# train-controller.net
KiCad netlist of a schematic drawn in EAGLE
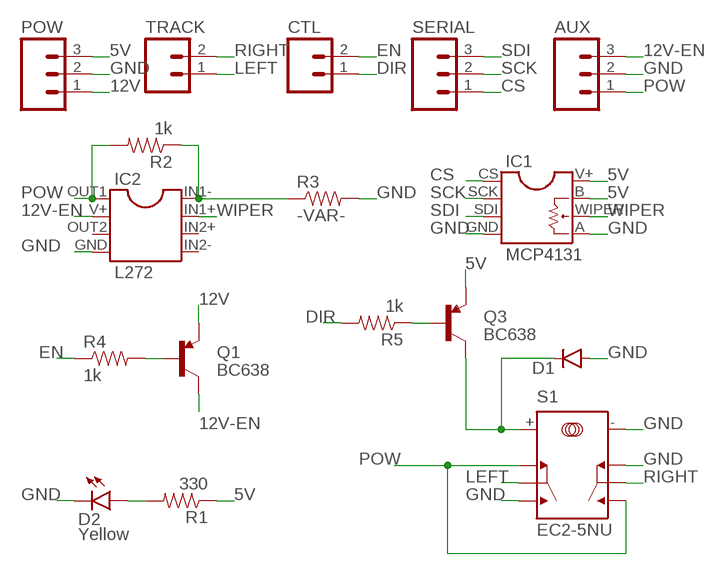
[diagram p0: schematic, sheet 1]

(export (version "E")
  (design (tool "Eeschema 10.0.6"))
  (components
    (comp (ref "AUX")
      (value "M03PTH")
      (footprint "eagle-import:1X03")
      (libsource (lib "eagle-import") (part "M03PTH"))
    )
    (comp (ref "CTL")
      (value "M02PTH")
      (footprint "eagle-import:1X02")
      (libsource (lib "eagle-import") (part "M02PTH"))
    )
    (comp (ref "D1")
      (value "DIODE1N4148")
      (footprint "eagle-import:DIODE-1N4148")
      (libsource (lib "eagle-import") (part "DIODE1N4148"))
    )
    (comp (ref "D2")
      (value "Yellow")
      (footprint "eagle-import:LED-EDGE")
      (libsource (lib "eagle-import") (part "LED-YELLOW0603"))
    )
    (comp (ref "IC1")
      (value "MCP4131")
      (footprint "eagle-import:MCP4131")
      (libsource (lib "eagle-import") (part "MCP4131"))
    )
    (comp (ref "IC2")
      (value "L272")
      (footprint "eagle-import:L272")
      (libsource (lib "eagle-import") (part "L272"))
    )
    (comp (ref "POW")
      (value "M03PTH")
      (footprint "eagle-import:1X03")
      (libsource (lib "eagle-import") (part "M03PTH"))
    )
    (comp (ref "Q1")
      (value "BC638")
      (footprint "eagle-import:TO-92")
      (libsource (lib "eagle-import") (part "TRANSISTOR_PNPTO92"))
    )
    (comp (ref "Q3")
      (value "BC638")
      (footprint "eagle-import:TO-92")
      (libsource (lib "eagle-import") (part "TRANSISTOR_PNPTO92"))
    )
    (comp (ref "R1")
      (value "330")
      (footprint "eagle-import:AXIAL-0.3")
      (libsource (lib "eagle-import") (part "1KOHM-1/4W-5%(PTH)"))
    )
    (comp (ref "R2")
      (value "1k")
      (footprint "eagle-import:AXIAL-0.3")
      (libsource (lib "eagle-import") (part "1KOHM-1/4W-5%(PTH)"))
    )
    (comp (ref "R3")
      (value "-VAR-")
      (footprint "eagle-import:AXIAL-0.3")
      (libsource (lib "eagle-import") (part "1KOHM-1/4W-5%(PTH)"))
    )
    (comp (ref "R4")
      (value "1k")
      (footprint "eagle-import:AXIAL-0.3")
      (libsource (lib "eagle-import") (part "1KOHM-1/4W-5%(PTH)"))
    )
    (comp (ref "R5")
      (value "1k")
      (footprint "eagle-import:AXIAL-0.3")
      (libsource (lib "eagle-import") (part "1KOHM-1/4W-5%(PTH)"))
    )
    (comp (ref "S1")
      (value "EC2-5NU")
      (footprint "eagle-import:EC2-5NU")
      (libsource (lib "eagle-import") (part "EC2-5NU"))
    )
    (comp (ref "SERIAL")
      (value "M03PTH")
      (footprint "eagle-import:1X03")
      (libsource (lib "eagle-import") (part "M03PTH"))
    )
    (comp (ref "TRACK")
      (value "M02PTH")
      (footprint "eagle-import:1X02")
      (libsource (lib "eagle-import") (part "M02PTH"))
    )
  )
  (nets
    (net (code "1") (name "/5V") (class "Default")
      (node (ref "IC1") (pin "B") (pinfunction "B_B") (pintype "bidirectional"))
      (node (ref "IC1") (pin "V+") (pinfunction "V+_V+") (pintype "bidirectional"))
      (node (ref "POW") (pin "3") (pinfunction "3_3") (pintype "passive"))
      (node (ref "Q3") (pin "1") (pinfunction "E_1") (pintype "passive"))
      (node (ref "R1") (pin "P$1") (pinfunction "1_P$1") (pintype "passive"))
    )
    (net (code "2") (name "/12V") (class "Default")
      (node (ref "POW") (pin "1") (pinfunction "1_1") (pintype "passive"))
      (node (ref "Q1") (pin "1") (pinfunction "E_1") (pintype "passive"))
    )
    (net (code "3") (name "/12V-EN") (class "Default")
      (node (ref "AUX") (pin "3") (pinfunction "3_3") (pintype "passive"))
      (node (ref "IC2") (pin "V+") (pinfunction "V+_V+") (pintype "bidirectional"))
      (node (ref "Q1") (pin "3") (pinfunction "C_3") (pintype "passive"))
    )
    (net (code "4") (name "/CS") (class "Default")
      (node (ref "IC1") (pin "CS") (pinfunction "CS_CS") (pintype "bidirectional"))
      (node (ref "SERIAL") (pin "1") (pinfunction "1_1") (pintype "passive"))
    )
    (net (code "5") (name "/DIR") (class "Default")
      (node (ref "CTL") (pin "1") (pinfunction "1_1") (pintype "passive"))
      (node (ref "R5") (pin "P$2") (pinfunction "2_P$2") (pintype "passive"))
    )
    (net (code "6") (name "/EN") (class "Default")
      (node (ref "CTL") (pin "2") (pinfunction "2_2") (pintype "passive"))
      (node (ref "R4") (pin "P$1") (pinfunction "1_P$1") (pintype "passive"))
    )
    (net (code "7") (name "/GND") (class "Default")
      (node (ref "AUX") (pin "2") (pinfunction "2_2") (pintype "passive"))
      (node (ref "D1") (pin "A") (pinfunction "A_A") (pintype "passive"))
      (node (ref "D2") (pin "C") (pinfunction "C_C") (pintype "passive"))
      (node (ref "IC1") (pin "A") (pinfunction "A_A") (pintype "bidirectional"))
      (node (ref "IC1") (pin "GND") (pinfunction "GND_GND") (pintype "bidirectional"))
      (node (ref "IC2") (pin "GND") (pinfunction "GND_GND") (pintype "bidirectional"))
      (node (ref "POW") (pin "2") (pinfunction "2_2") (pintype "passive"))
      (node (ref "R3") (pin "P$2") (pinfunction "2_P$2") (pintype "passive"))
      (node (ref "S1") (pin "-") (pinfunction "-_-") (pintype "power_in"))
      (node (ref "S1") (pin "NC2") (pinfunction "NC2_NC2") (pintype "bidirectional"))
      (node (ref "S1") (pin "NO1") (pinfunction "NO1_NO1") (pintype "bidirectional"))
    )
    (net (code "8") (name "/LEFT") (class "Default")
      (node (ref "S1") (pin "COM1") (pinfunction "COM1_COM1") (pintype "bidirectional"))
      (node (ref "TRACK") (pin "1") (pinfunction "1_1") (pintype "passive"))
    )
    (net (code "9") (name "/POW") (class "Default")
      (node (ref "AUX") (pin "1") (pinfunction "1_1") (pintype "passive"))
      (node (ref "IC2") (pin "OUT1") (pinfunction "OUT1_OUT1") (pintype "bidirectional"))
      (node (ref "R2") (pin "P$2") (pinfunction "2_P$2") (pintype "passive"))
      (node (ref "S1") (pin "NC1") (pinfunction "NC1_NC1") (pintype "bidirectional"))
      (node (ref "S1") (pin "NO2") (pinfunction "NO2_NO2") (pintype "bidirectional"))
    )
    (net (code "10") (name "/RIGHT") (class "Default")
      (node (ref "S1") (pin "COM2") (pinfunction "COM2_COM2") (pintype "bidirectional"))
      (node (ref "TRACK") (pin "2") (pinfunction "2_2") (pintype "passive"))
    )
    (net (code "11") (name "/SCK") (class "Default")
      (node (ref "IC1") (pin "SCK") (pinfunction "SCK_SCK") (pintype "bidirectional"))
      (node (ref "SERIAL") (pin "2") (pinfunction "2_2") (pintype "passive"))
    )
    (net (code "12") (name "/SDI") (class "Default")
      (node (ref "IC1") (pin "SDI") (pinfunction "SDI_SDI") (pintype "bidirectional"))
      (node (ref "SERIAL") (pin "3") (pinfunction "3_3") (pintype "passive"))
    )
    (net (code "13") (name "/WIPER") (class "Default")
      (node (ref "IC1") (pin "WIPER") (pinfunction "WIPER_WIPER") (pintype "bidirectional"))
      (node (ref "IC2") (pin "IN1+") (pinfunction "IN1+_IN1+") (pintype "bidirectional"))
    )
    (net (code "14") (name "Net-(Q1-B)") (class "Default")
      (node (ref "Q1") (pin "2") (pinfunction "B_2") (pintype "passive"))
      (node (ref "R4") (pin "P$2") (pinfunction "2_P$2") (pintype "passive"))
    )
    (net (code "15") (name "Net-(Q3-B)") (class "Default")
      (node (ref "Q3") (pin "2") (pinfunction "B_2") (pintype "passive"))
      (node (ref "R5") (pin "P$1") (pinfunction "1_P$1") (pintype "passive"))
    )
    (net (code "16") (name "Net-(Q3-C)") (class "Default")
      (node (ref "D1") (pin "C") (pinfunction "C_C") (pintype "passive"))
      (node (ref "Q3") (pin "3") (pinfunction "C_3") (pintype "passive"))
      (node (ref "S1") (pin "+") (pinfunction "+_+") (pintype "power_in"))
    )
    (net (code "17") (name "Net-(R1-2)") (class "Default")
      (node (ref "D2") (pin "A") (pinfunction "A_A") (pintype "passive"))
      (node (ref "R1") (pin "P$2") (pinfunction "2_P$2") (pintype "passive"))
    )
    (net (code "18") (name "Net-(R2-1)") (class "Default")
      (node (ref "IC2") (pin "IN1-") (pinfunction "IN1-_IN1-") (pintype "bidirectional"))
      (node (ref "R2") (pin "P$1") (pinfunction "1_P$1") (pintype "passive"))
      (node (ref "R3") (pin "P$1") (pinfunction "1_P$1") (pintype "passive"))
    )
    (net (code "19") (name "unconnected-(IC2-PadIN2+)") (class "Default")
      (node (ref "IC2") (pin "IN2+") (pinfunction "IN2+_IN2+") (pintype "bidirectional"))
    )
    (net (code "20") (name "unconnected-(IC2-PadIN2-)") (class "Default")
      (node (ref "IC2") (pin "IN2-") (pinfunction "IN2-_IN2-") (pintype "bidirectional"))
    )
    (net (code "21") (name "unconnected-(IC2-PadOUT2)") (class "Default")
      (node (ref "IC2") (pin "OUT2") (pinfunction "OUT2_OUT2") (pintype "bidirectional"))
    )
  )
)
